# Converter_3V3-1V.net
KiCad netlist of a schematic drawn in Altium Designer
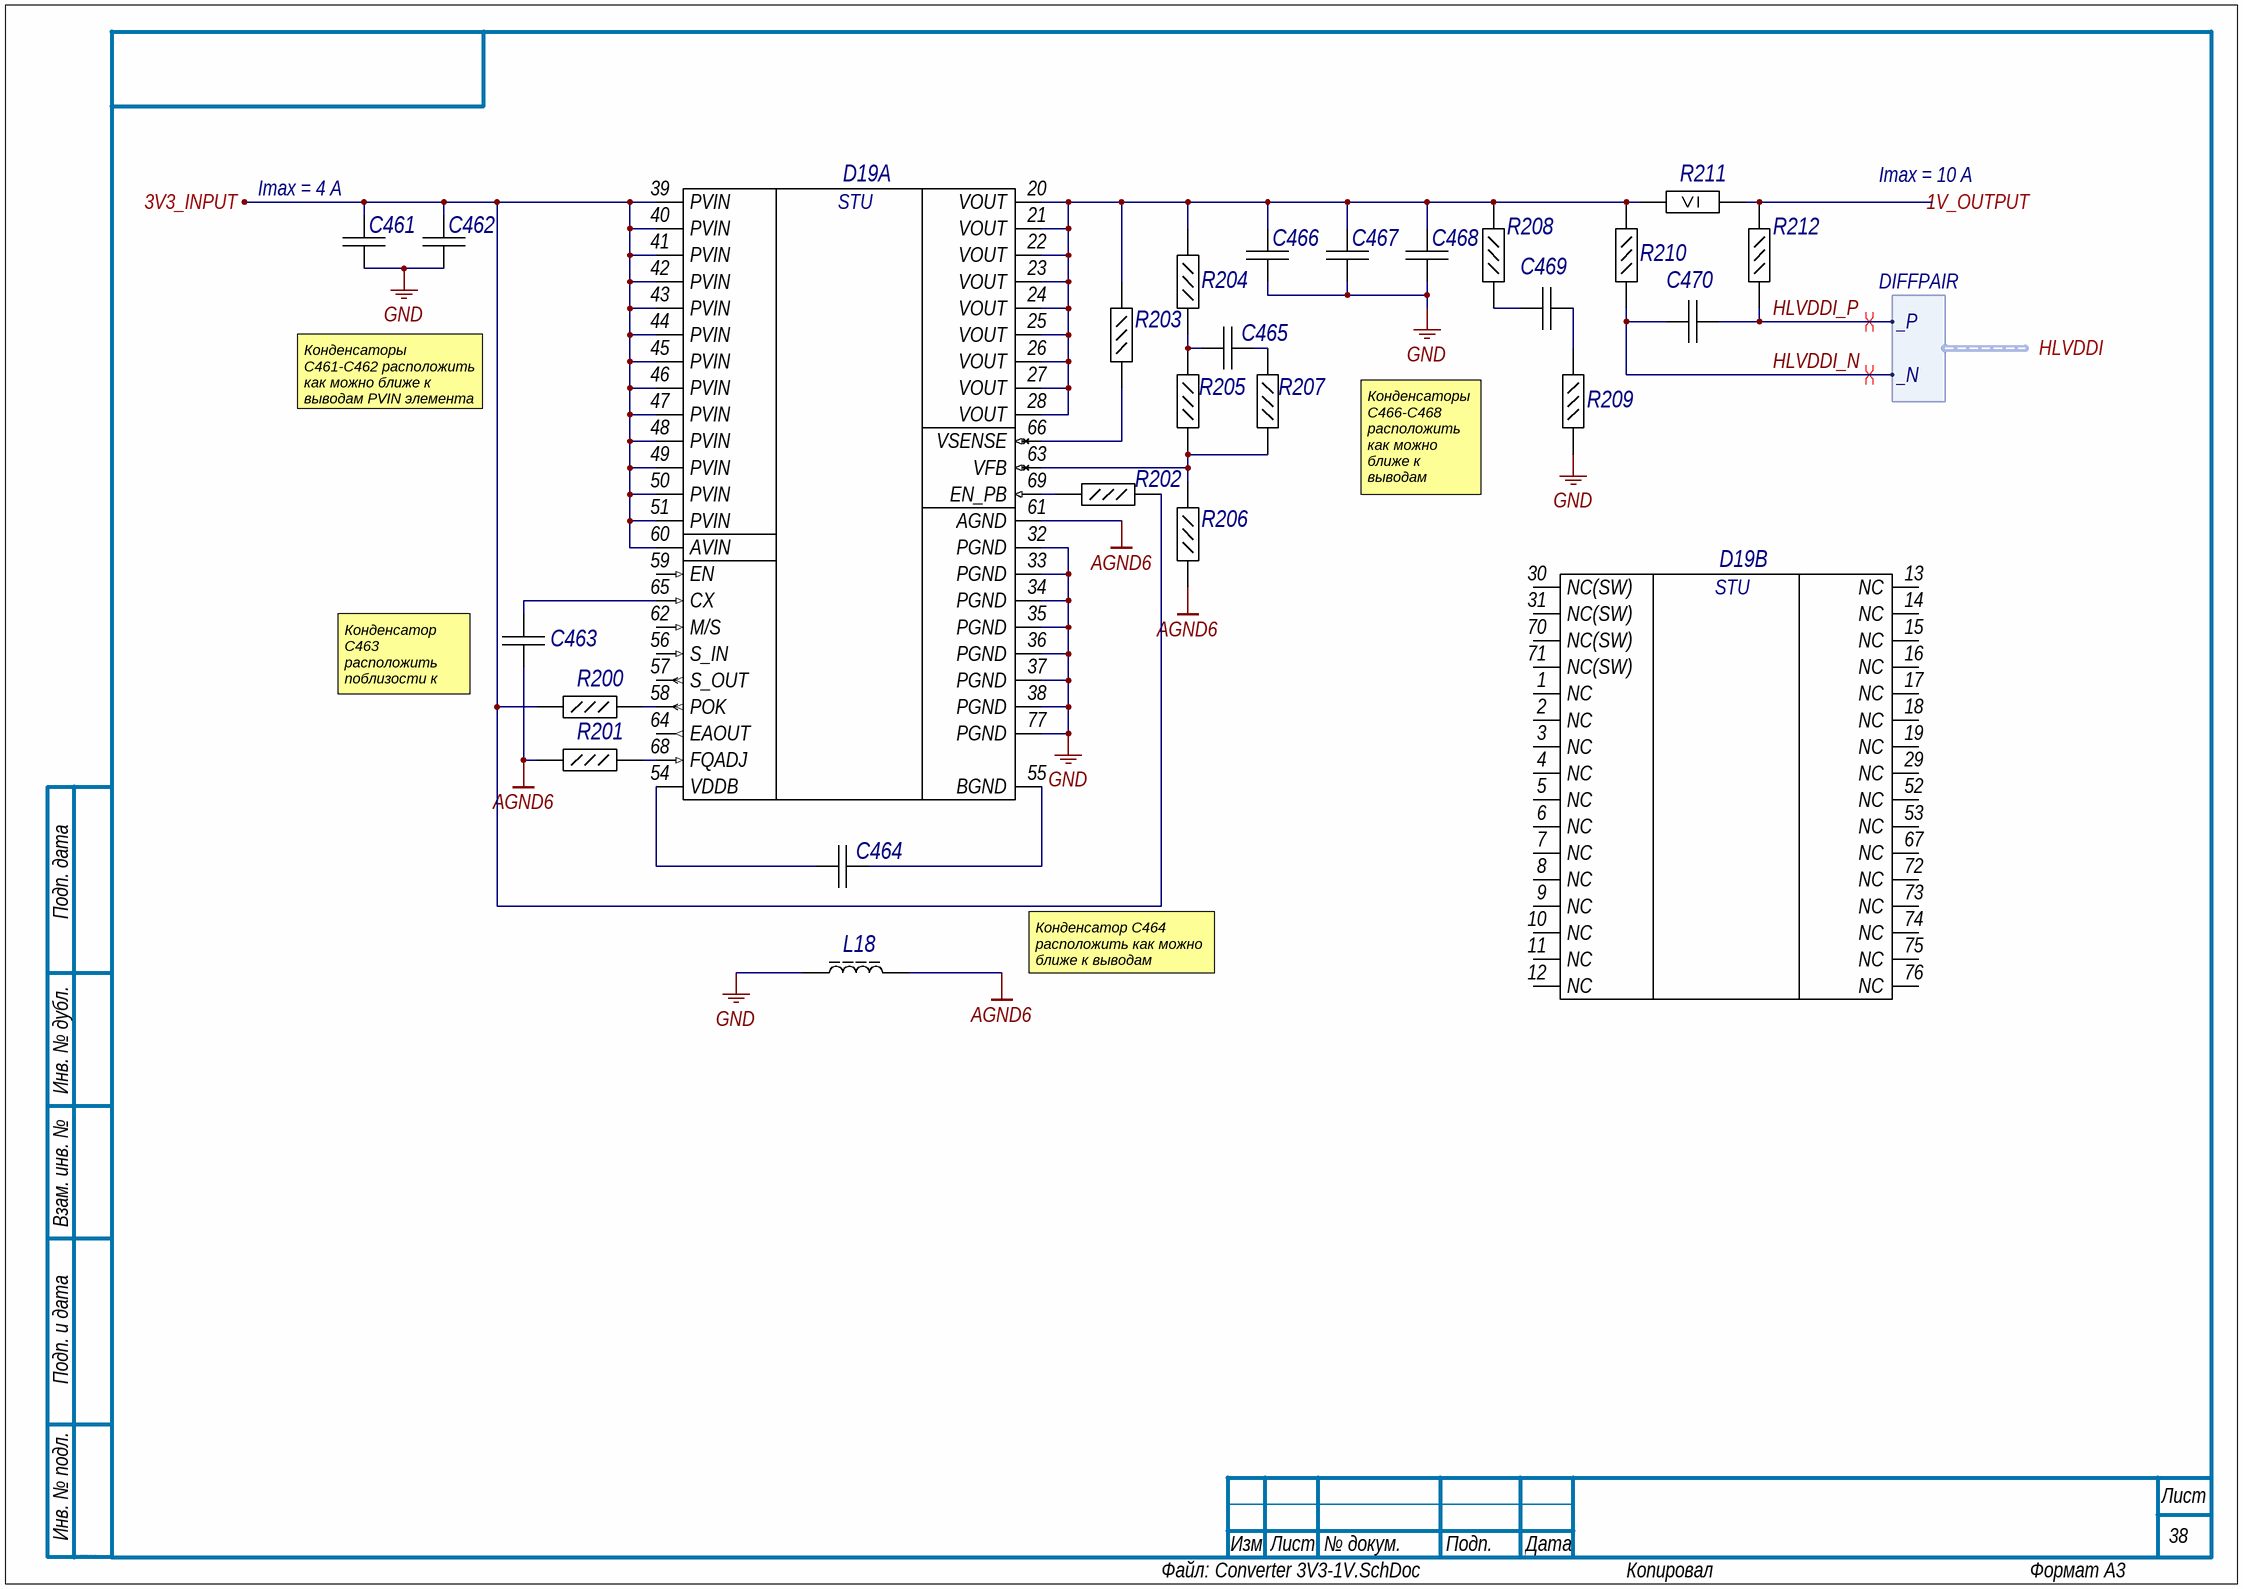
[diagram p0: Converter 3V3-1V.SchDoc]

(export (version "E")
  (design (tool "Eeschema 10.0.6"))
  (components
    (comp (ref "C461")
      (value "C3216X5R1A476M160AB")
      (footprint "CAPC3216X180X20ML20")
      (description "Chip Capacitor, 47 uF, +/- 20%, 10 V, -55 to 85 degC, 1206 (3216 Metric), RoHS, Tape and Reel")
      (fields (field (name "TOLERANCE") "20%"))
      (libsource (lib "MiniPC DB") (part "CAP_NP"))
    )
    (comp (ref "C462")
      (value "C3216X5R1A476M160AB")
      (footprint "CAPC3216X180X20ML20")
      (description "Chip Capacitor, 47 uF, +/- 20%, 10 V, -55 to 85 degC, 1206 (3216 Metric), RoHS, Tape and Reel")
      (fields (field (name "TOLERANCE") "20%"))
      (libsource (lib "MiniPC DB") (part "CAP_NP"))
    )
    (comp (ref "C463")
      (value "VJ0402Y153JXQPW1BC")
      (footprint "CAPC1005X55X23ML05T8")
      (description "Chip Capacitor, 15 nF, +/- 5%, 10 V, -55 to 125 degC, 0402 (1005 Metric), RoHS, Tape and Reel")
      (fields (field (name "TOLERANCE") "5%"))
      (libsource (lib "MiniPC DB") (part "CAP_NP"))
    )
    (comp (ref "C464")
      (value "GRM155R61A224KE19D")
      (footprint "CAPC1005X55X25NL05T10")
      (description "Chip Capacitor, 220 nF, +/- 10%, 10 V, -55 to 85 degC, 0402 (1005 Metric), RoHS, Tape and Reel")
      (fields (field (name "TOLERANCE") "10%") (field (name "MANUFACTURER") "Basic Passives"))
      (libsource (lib "MiniPC DB") (part "CAP_NP"))
    )
    (comp (ref "C465")
      (value "ECJ-0EC1H270J")
      (footprint "CAPC1005X55X20ML5T10")
      (description "Chip Capacitor, 27 pF, +/- 5%, 50 V, -55 to 125 degC, 0402 (1005 Metric), RoHS, Tape and Reel")
      (fields (field (name "TOLERANCE") "5%"))
      (libsource (lib "MiniPC DB") (part "CAP_NP"))
    )
    (comp (ref "C466")
      (value "C3216X5R1A476M160AB")
      (footprint "CAPC3216X180X20ML20")
      (description "Chip Capacitor, 47 uF, +/- 20%, 10 V, -55 to 85 degC, 1206 (3216 Metric), RoHS, Tape and Reel")
      (fields (field (name "TOLERANCE") "20%"))
      (libsource (lib "MiniPC DB") (part "CAP_NP"))
    )
    (comp (ref "C467")
      (value "C3216X5R1A476M160AB")
      (footprint "CAPC3216X180X20ML20")
      (description "Chip Capacitor, 47 uF, +/- 20%, 10 V, -55 to 85 degC, 1206 (3216 Metric), RoHS, Tape and Reel")
      (fields (field (name "TOLERANCE") "20%"))
      (libsource (lib "MiniPC DB") (part "CAP_NP"))
    )
    (comp (ref "C468")
      (value "C3216X5R1A476M160AB")
      (footprint "CAPC3216X180X20ML20")
      (description "Chip Capacitor, 47 uF, +/- 20%, 10 V, -55 to 85 degC, 1206 (3216 Metric), RoHS, Tape and Reel")
      (fields (field (name "TOLERANCE") "20%"))
      (libsource (lib "MiniPC DB") (part "CAP_NP"))
    )
    (comp (ref "C469")
      (value "GRM155R61A224KE19D")
      (footprint "CAPC1005X55X25NL05T10")
      (description "Chip Capacitor, 220 nF, +/- 10%, 10 V, -55 to 85 degC, 0402 (1005 Metric), RoHS, Tape and Reel")
      (fields (field (name "TOLERANCE") "10%") (field (name "MANUFACTURER") "Basic Passives"))
      (libsource (lib "MiniPC DB") (part "CAP_NP"))
    )
    (comp (ref "C470")
      (value "CGB2A1X5R1E105K033BC")
      (footprint "CAPC1005X33X10LL5")
      (description "Chip Capacitor, 1 uF, +/- 10%, 25 V, -55 to 85 degC, 0402 (1005 Metric), RoHS, Tape and Reel")
      (fields (field (name "TOLERANCE") "10%"))
      (libsource (lib "MiniPC DB") (part "CAP_NP"))
    )
    (comp (ref "D19")
      (value "EN63A0QI")
      (footprint "ALTR-QFN-76_A-305_V")
      (libsource (lib "MiniPC DB") (part "EN63A0QI"))
    )
    (comp (ref "L18")
      (value "742792609")
      (footprint "SMD-0603")
      (description "SMD EMI Suppression Ferrite Bead WE-CBF, Z = 30 Ohm")
      (libsource (lib "MiniPC DB") (part "Choke"))
    )
    (comp (ref "R200")
      (value "ERJ-2RKF1003X")
      (footprint "RESC1005X40X25LL05T05")
      (description "Chip Resistor, 100 KOhm, +/- 1%, 100 mW, -55 to 155 degC, 0402 (1005 Metric), RoHS, Tape and Reel")
      (fields (field (name "TOLERANCE") "1%") (field (name "MANUFACTURER") "Basic Passives"))
      (libsource (lib "MiniPC DB") (part "RES-0.05"))
    )
    (comp (ref "R201")
      (value "CRCW04023K57FKED")
      (footprint "RESC1005X40X25LL05T05")
      (description "Chip Resistor, 3.57 KOhm, +/- 1%, 63 mW, -55 to 155 degC, 0402 (1005 Metric), RoHS, Tape and Reel")
      (fields (field (name "TOLERANCE") "1%"))
      (libsource (lib "MiniPC DB") (part "RES-0.05"))
    )
    (comp (ref "R202")
      (value "ERJ-2RKF1002X")
      (footprint "RESC1005X40X25LL05T05")
      (description "Chip Resistor, 10 KOhm, +/- 1%, 100 mW, -55 to 155 degC, 0402 (1005 Metric), RoHS, Tape and Reel")
      (fields (field (name "TOLERANCE") "1%") (field (name "MANUFACTURER") "Basic Passives"))
      (libsource (lib "MiniPC DB") (part "RES-0.05"))
    )
    (comp (ref "R203")
      (value "ERJ-2GE0R00X")
      (footprint "RESC1005X40X25LL05T05")
      (description "Chip Resistor, 0 mOhm, +/- 5%, 100 mW, -55 to 155 degC, 0402 (1005 Metric), RoHS, Tape and Reel")
      (fields (field (name "TOLERANCE") "5%") (field (name "MANUFACTURER") "Basic Passives"))
      (libsource (lib "") (part "RES-0.05_2"))
    )
    (comp (ref "R204")
      (value "ERJ-2GE0R00X")
      (footprint "RESC1005X40X25LL05T05")
      (description "Chip Resistor, 0 mOhm, +/- 5%, 100 mW, -55 to 155 degC, 0402 (1005 Metric), RoHS, Tape and Reel")
      (fields (field (name "TOLERANCE") "5%") (field (name "MANUFACTURER") "Basic Passives"))
      (libsource (lib "") (part "RES-0.05_1"))
    )
    (comp (ref "R205")
      (value "CRCW0402160KFKED")
      (footprint "RESC1005X40X25LL05T05")
      (description "Chip Resistor, 160 KOhm, +/- 1%, 63 mW, -55 to 155 degC, 0402 (1005 Metric), RoHS, Tape and Reel")
      (fields (field (name "TOLERANCE") "1%") (field (name "MANUFACTURER") "Basic Passives"))
      (libsource (lib "") (part "RES-0.05_1"))
    )
    (comp (ref "R206")
      (value "ERJ-2RKF2263X")
      (footprint "RESC1005X40X25LL05T05")
      (description "Chip Resistor, 226 KOhm, +/- 1%, 100 mW, -55 to 155 degC, 0402 (1005 Metric), RoHS, Tape and Reel")
      (fields (field (name "TOLERANCE") "1%") (field (name "MANUFACTURER") "Basic Passives"))
      (libsource (lib "") (part "RES-0.05_1"))
    )
    (comp (ref "R207")
      (value "ERJ-2RKF1202X")
      (footprint "RESC1005X40X25LL05T05")
      (description "Chip Resistor, 12 KOhm, +/- 1%, 0.1 W, -55 to 155 degC, 0402 (1005 Metric), RoHS, Tape and Reel")
      (fields (field (name "TOLERANCE") "1%"))
      (libsource (lib "") (part "RES-0.05_1"))
    )
    (comp (ref "R208")
      (value "ERJ-2RKF1000X")
      (footprint "RESC1005X40X25LL05T05")
      (description "Chip Resistor, 100 Ohm, +/- 1%, 100 mW, -55 to 155 degC, 0402 (1005 Metric), RoHS, Tape and Reel")
      (fields (field (name "TOLERANCE") "1%") (field (name "MANUFACTURER") "Basic Passives"))
      (libsource (lib "") (part "RES-0.05_1"))
    )
    (comp (ref "R209")
      (value "ERJ-2RKF1000X")
      (footprint "RESC1005X40X25LL05T05")
      (description "Chip Resistor, 100 Ohm, +/- 1%, 100 mW, -55 to 155 degC, 0402 (1005 Metric), RoHS, Tape and Reel")
      (fields (field (name "TOLERANCE") "1%") (field (name "MANUFACTURER") "Basic Passives"))
      (libsource (lib "") (part "RES-0.05_2"))
    )
    (comp (ref "R210")
      (value "ERJ-2RKF1002X")
      (footprint "RESC1005X40X25LL05T05")
      (description "Chip Resistor, 10 KOhm, +/- 1%, 100 mW, -55 to 155 degC, 0402 (1005 Metric), RoHS, Tape and Reel")
      (fields (field (name "TOLERANCE") "1%") (field (name "MANUFACTURER") "Basic Passives"))
      (libsource (lib "") (part "RES-0.05_2"))
    )
    (comp (ref "R211")
      (value "CSS2725FTL250")
      (footprint "STAC-CSS2725-099H_V")
      (description "Chip Resistor, 0.25 mOhm, +/- 1%, 4 W, -55 to 225 degC, 2725 (6865 Metric), RoHS, Tape and Reel")
      (fields (field (name "TOLERANCE") "1%"))
      (libsource (lib "MiniPC DB") (part "RES-4"))
    )
    (comp (ref "R212")
      (value "ERJ-2RKF1002X")
      (footprint "RESC1005X40X25LL05T05")
      (description "Chip Resistor, 10 KOhm, +/- 1%, 100 mW, -55 to 155 degC, 0402 (1005 Metric), RoHS, Tape and Reel")
      (fields (field (name "TOLERANCE") "1%") (field (name "MANUFACTURER") "Basic Passives"))
      (libsource (lib "") (part "RES-0.05_2"))
    )
  )
  (nets
    (net (code "2") (name "/1V_OUTPUT") (class "Default")
      (node (ref "R211") (pin "1") (pinfunction "1_1") (pintype "passive"))
      (node (ref "R212") (pin "2") (pinfunction "2_2") (pintype "passive"))
    )
    (net (code "3") (name "/3V3_INPUT") (class "Default")
      (node (ref "C461") (pin "2") (pinfunction "2_2") (pintype "passive"))
      (node (ref "C462") (pin "2") (pinfunction "2_2") (pintype "passive"))
      (node (ref "D19") (pin "39") (pinfunction "PVIN_39") (pintype "power_in"))
      (node (ref "D19") (pin "40") (pinfunction "PVIN_40") (pintype "power_in"))
      (node (ref "D19") (pin "41") (pinfunction "PVIN_41") (pintype "power_in"))
      (node (ref "D19") (pin "42") (pinfunction "PVIN_42") (pintype "power_in"))
      (node (ref "D19") (pin "43") (pinfunction "PVIN_43") (pintype "power_in"))
      (node (ref "D19") (pin "44") (pinfunction "PVIN_44") (pintype "power_in"))
      (node (ref "D19") (pin "45") (pinfunction "PVIN_45") (pintype "power_in"))
      (node (ref "D19") (pin "46") (pinfunction "PVIN_46") (pintype "power_in"))
      (node (ref "D19") (pin "47") (pinfunction "PVIN_47") (pintype "power_in"))
      (node (ref "D19") (pin "48") (pinfunction "PVIN_48") (pintype "power_in"))
      (node (ref "D19") (pin "49") (pinfunction "PVIN_49") (pintype "power_in"))
      (node (ref "D19") (pin "50") (pinfunction "PVIN_50") (pintype "power_in"))
      (node (ref "D19") (pin "51") (pinfunction "PVIN_51") (pintype "power_in"))
      (node (ref "D19") (pin "60") (pinfunction "AVIN_60") (pintype "power_in"))
      (node (ref "R200") (pin "2") (pinfunction "2_2") (pintype "passive"))
      (node (ref "R202") (pin "1") (pinfunction "1_1") (pintype "passive"))
    )
    (net (code "4") (name "/HLVDDI_N") (class "Default")
      (node (ref "C470") (pin "1") (pinfunction "1_1") (pintype "passive"))
      (node (ref "R210") (pin "1") (pinfunction "1_1") (pintype "passive"))
    )
    (net (code "5") (name "/HLVDDI_P") (class "Default")
      (node (ref "C470") (pin "2") (pinfunction "2_2") (pintype "passive"))
      (node (ref "R212") (pin "1") (pinfunction "1_1") (pintype "passive"))
    )
    (net (code "7") (name "AGND6") (class "Default")
      (node (ref "C463") (pin "1") (pinfunction "1_1") (pintype "passive"))
      (node (ref "D19") (pin "61") (pinfunction "AGND_61") (pintype "power_in"))
      (node (ref "L18") (pin "2") (pinfunction "2_2") (pintype "passive"))
      (node (ref "R201") (pin "2") (pinfunction "2_2") (pintype "passive"))
      (node (ref "R206") (pin "2") (pinfunction "2_2") (pintype "passive"))
    )
    (net (code "8") (name "GND") (class "Default")
      (node (ref "C461") (pin "1") (pinfunction "1_1") (pintype "passive"))
      (node (ref "C462") (pin "1") (pinfunction "1_1") (pintype "passive"))
      (node (ref "C466") (pin "1") (pinfunction "1_1") (pintype "passive"))
      (node (ref "C467") (pin "1") (pinfunction "1_1") (pintype "passive"))
      (node (ref "C468") (pin "1") (pinfunction "1_1") (pintype "passive"))
      (node (ref "D19") (pin "32") (pinfunction "PGND_32") (pintype "power_in"))
      (node (ref "D19") (pin "33") (pinfunction "PGND_33") (pintype "power_in"))
      (node (ref "D19") (pin "34") (pinfunction "PGND_34") (pintype "power_in"))
      (node (ref "D19") (pin "35") (pinfunction "PGND_35") (pintype "power_in"))
      (node (ref "D19") (pin "36") (pinfunction "PGND_36") (pintype "power_in"))
      (node (ref "D19") (pin "37") (pinfunction "PGND_37") (pintype "power_in"))
      (node (ref "D19") (pin "38") (pinfunction "PGND_38") (pintype "power_in"))
      (node (ref "D19") (pin "77") (pinfunction "PGND_77") (pintype "power_in"))
      (node (ref "L18") (pin "1") (pinfunction "1_1") (pintype "passive"))
      (node (ref "R209") (pin "1") (pinfunction "1_1") (pintype "passive"))
    )
    (net (code "9") (name "Net-(C465-Pad1)") (class "Default")
      (node (ref "C465") (pin "1") (pinfunction "1_1") (pintype "passive"))
      (node (ref "R204") (pin "2") (pinfunction "2_2") (pintype "passive"))
      (node (ref "R205") (pin "1") (pinfunction "1_1") (pintype "passive"))
    )
    (net (code "10") (name "Net-(C465-Pad2)") (class "Default")
      (node (ref "C465") (pin "2") (pinfunction "2_2") (pintype "passive"))
      (node (ref "R207") (pin "1") (pinfunction "1_1") (pintype "passive"))
    )
    (net (code "11") (name "Net-(C466-Pad2)") (class "Default")
      (node (ref "C466") (pin "2") (pinfunction "2_2") (pintype "passive"))
      (node (ref "C467") (pin "2") (pinfunction "2_2") (pintype "passive"))
      (node (ref "C468") (pin "2") (pinfunction "2_2") (pintype "passive"))
      (node (ref "D19") (pin "20") (pinfunction "VOUT_20") (pintype "power_in"))
      (node (ref "D19") (pin "21") (pinfunction "VOUT_21") (pintype "power_in"))
      (node (ref "D19") (pin "22") (pinfunction "VOUT_22") (pintype "power_in"))
      (node (ref "D19") (pin "23") (pinfunction "VOUT_23") (pintype "power_in"))
      (node (ref "D19") (pin "24") (pinfunction "VOUT_24") (pintype "power_in"))
      (node (ref "D19") (pin "25") (pinfunction "VOUT_25") (pintype "power_in"))
      (node (ref "D19") (pin "26") (pinfunction "VOUT_26") (pintype "power_in"))
      (node (ref "D19") (pin "27") (pinfunction "VOUT_27") (pintype "power_in"))
      (node (ref "D19") (pin "28") (pinfunction "VOUT_28") (pintype "power_in"))
      (node (ref "R203") (pin "2") (pinfunction "2_2") (pintype "passive"))
      (node (ref "R204") (pin "1") (pinfunction "1_1") (pintype "passive"))
      (node (ref "R208") (pin "1") (pinfunction "1_1") (pintype "passive"))
      (node (ref "R210") (pin "2") (pinfunction "2_2") (pintype "passive"))
      (node (ref "R211") (pin "2") (pinfunction "2_2") (pintype "passive"))
    )
    (net (code "12") (name "Net-(C469-Pad1)") (class "Default")
      (node (ref "C469") (pin "1") (pinfunction "1_1") (pintype "passive"))
      (node (ref "R208") (pin "2") (pinfunction "2_2") (pintype "passive"))
    )
    (net (code "13") (name "Net-(C469-Pad2)") (class "Default")
      (node (ref "C469") (pin "2") (pinfunction "2_2") (pintype "passive"))
      (node (ref "R209") (pin "2") (pinfunction "2_2") (pintype "passive"))
    )
    (net (code "14") (name "Net-(D19A-BGND)") (class "Default")
      (node (ref "C464") (pin "1") (pinfunction "1_1") (pintype "passive"))
      (node (ref "D19") (pin "55") (pinfunction "BGND_55") (pintype "power_in"))
    )
    (net (code "15") (name "Net-(D19A-CX)") (class "Default")
      (node (ref "C463") (pin "2") (pinfunction "2_2") (pintype "passive"))
      (node (ref "D19") (pin "65") (pinfunction "CX_65") (pintype "input"))
    )
    (net (code "16") (name "Net-(D19A-EN_PB)") (class "Default")
      (node (ref "D19") (pin "69") (pinfunction "EN_PB_69") (pintype "input"))
      (node (ref "R202") (pin "2") (pinfunction "2_2") (pintype "passive"))
    )
    (net (code "17") (name "Net-(D19A-FQADJ)") (class "Default")
      (node (ref "D19") (pin "68") (pinfunction "FQADJ_68") (pintype "input"))
      (node (ref "R201") (pin "1") (pinfunction "1_1") (pintype "passive"))
    )
    (net (code "18") (name "Net-(D19A-POK)") (class "Default")
      (node (ref "D19") (pin "58") (pinfunction "POK_58") (pintype "output"))
      (node (ref "R200") (pin "1") (pinfunction "1_1") (pintype "passive"))
    )
    (net (code "19") (name "Net-(D19A-VDDB)") (class "Default")
      (node (ref "C464") (pin "2") (pinfunction "2_2") (pintype "passive"))
      (node (ref "D19") (pin "54") (pinfunction "VDDB_54") (pintype "power_in"))
    )
    (net (code "20") (name "Net-(D19A-VFB)") (class "Default")
      (node (ref "D19") (pin "63") (pinfunction "VFB_63") (pintype "input"))
      (node (ref "R205") (pin "2") (pinfunction "2_2") (pintype "passive"))
      (node (ref "R206") (pin "1") (pinfunction "1_1") (pintype "passive"))
      (node (ref "R207") (pin "2") (pinfunction "2_2") (pintype "passive"))
    )
    (net (code "21") (name "Net-(D19A-VSENSE)") (class "Default")
      (node (ref "D19") (pin "66") (pinfunction "VSENSE_66") (pintype "input"))
      (node (ref "R203") (pin "1") (pinfunction "1_1") (pintype "passive"))
    )
    (net (code "22") (name "unconnected-(D19A-EAOUT-Pad64)") (class "Default")
      (node (ref "D19") (pin "64") (pinfunction "EAOUT_64") (pintype "output"))
    )
    (net (code "23") (name "unconnected-(D19A-EN-Pad59)") (class "Default")
      (node (ref "D19") (pin "59") (pinfunction "EN_59") (pintype "input"))
    )
    (net (code "24") (name "unconnected-(D19A-M{slash}S-Pad62)") (class "Default")
      (node (ref "D19") (pin "62") (pinfunction "M/S_62") (pintype "input"))
    )
    (net (code "25") (name "unconnected-(D19A-S_IN-Pad56)") (class "Default")
      (node (ref "D19") (pin "56") (pinfunction "S_IN_56") (pintype "input"))
    )
    (net (code "26") (name "unconnected-(D19A-S_OUT-Pad57)") (class "Default")
      (node (ref "D19") (pin "57") (pinfunction "S_OUT_57") (pintype "output"))
    )
    (net (code "27") (name "unconnected-(D19B-NC(SW)-Pad30)") (class "Default")
      (node (ref "D19") (pin "30") (pinfunction "NC(SW)_30") (pintype "passive"))
    )
    (net (code "28") (name "unconnected-(D19B-NC(SW)-Pad31)") (class "Default")
      (node (ref "D19") (pin "31") (pinfunction "NC(SW)_31") (pintype "passive"))
    )
    (net (code "29") (name "unconnected-(D19B-NC(SW)-Pad70)") (class "Default")
      (node (ref "D19") (pin "70") (pinfunction "NC(SW)_70") (pintype "passive"))
    )
    (net (code "30") (name "unconnected-(D19B-NC(SW)-Pad71)") (class "Default")
      (node (ref "D19") (pin "71") (pinfunction "NC(SW)_71") (pintype "passive"))
    )
    (net (code "31") (name "unconnected-(D19B-NC-Pad1)") (class "Default")
      (node (ref "D19") (pin "1") (pinfunction "NC_1") (pintype "passive"))
    )
    (net (code "32") (name "unconnected-(D19B-NC-Pad2)") (class "Default")
      (node (ref "D19") (pin "2") (pinfunction "NC_2") (pintype "passive"))
    )
    (net (code "33") (name "unconnected-(D19B-NC-Pad3)") (class "Default")
      (node (ref "D19") (pin "3") (pinfunction "NC_3") (pintype "passive"))
    )
    (net (code "34") (name "unconnected-(D19B-NC-Pad4)") (class "Default")
      (node (ref "D19") (pin "4") (pinfunction "NC_4") (pintype "passive"))
    )
    (net (code "35") (name "unconnected-(D19B-NC-Pad5)") (class "Default")
      (node (ref "D19") (pin "5") (pinfunction "NC_5") (pintype "passive"))
    )
    (net (code "36") (name "unconnected-(D19B-NC-Pad6)") (class "Default")
      (node (ref "D19") (pin "6") (pinfunction "NC_6") (pintype "passive"))
    )
    (net (code "37") (name "unconnected-(D19B-NC-Pad7)") (class "Default")
      (node (ref "D19") (pin "7") (pinfunction "NC_7") (pintype "passive"))
    )
    (net (code "38") (name "unconnected-(D19B-NC-Pad8)") (class "Default")
      (node (ref "D19") (pin "8") (pinfunction "NC_8") (pintype "passive"))
    )
    (net (code "39") (name "unconnected-(D19B-NC-Pad9)") (class "Default")
      (node (ref "D19") (pin "9") (pinfunction "NC_9") (pintype "passive"))
    )
    (net (code "40") (name "unconnected-(D19B-NC-Pad10)") (class "Default")
      (node (ref "D19") (pin "10") (pinfunction "NC_10") (pintype "passive"))
    )
    (net (code "41") (name "unconnected-(D19B-NC-Pad11)") (class "Default")
      (node (ref "D19") (pin "11") (pinfunction "NC_11") (pintype "passive"))
    )
    (net (code "42") (name "unconnected-(D19B-NC-Pad12)") (class "Default")
      (node (ref "D19") (pin "12") (pinfunction "NC_12") (pintype "passive"))
    )
    (net (code "43") (name "unconnected-(D19B-NC-Pad13)") (class "Default")
      (node (ref "D19") (pin "13") (pinfunction "NC_13") (pintype "passive"))
    )
    (net (code "44") (name "unconnected-(D19B-NC-Pad14)") (class "Default")
      (node (ref "D19") (pin "14") (pinfunction "NC_14") (pintype "passive"))
    )
    (net (code "45") (name "unconnected-(D19B-NC-Pad15)") (class "Default")
      (node (ref "D19") (pin "15") (pinfunction "NC_15") (pintype "passive"))
    )
    (net (code "46") (name "unconnected-(D19B-NC-Pad16)") (class "Default")
      (node (ref "D19") (pin "16") (pinfunction "NC_16") (pintype "passive"))
    )
    (net (code "47") (name "unconnected-(D19B-NC-Pad17)") (class "Default")
      (node (ref "D19") (pin "17") (pinfunction "NC_17") (pintype "passive"))
    )
    (net (code "48") (name "unconnected-(D19B-NC-Pad18)") (class "Default")
      (node (ref "D19") (pin "18") (pinfunction "NC_18") (pintype "passive"))
    )
    (net (code "49") (name "unconnected-(D19B-NC-Pad19)") (class "Default")
      (node (ref "D19") (pin "19") (pinfunction "NC_19") (pintype "passive"))
    )
    (net (code "50") (name "unconnected-(D19B-NC-Pad29)") (class "Default")
      (node (ref "D19") (pin "29") (pinfunction "NC_29") (pintype "passive"))
    )
    (net (code "51") (name "unconnected-(D19B-NC-Pad52)") (class "Default")
      (node (ref "D19") (pin "52") (pinfunction "NC_52") (pintype "passive"))
    )
    (net (code "52") (name "unconnected-(D19B-NC-Pad53)") (class "Default")
      (node (ref "D19") (pin "53") (pinfunction "NC_53") (pintype "passive"))
    )
    (net (code "53") (name "unconnected-(D19B-NC-Pad67)") (class "Default")
      (node (ref "D19") (pin "67") (pinfunction "NC_67") (pintype "passive"))
    )
    (net (code "54") (name "unconnected-(D19B-NC-Pad72)") (class "Default")
      (node (ref "D19") (pin "72") (pinfunction "NC_72") (pintype "passive"))
    )
    (net (code "55") (name "unconnected-(D19B-NC-Pad73)") (class "Default")
      (node (ref "D19") (pin "73") (pinfunction "NC_73") (pintype "passive"))
    )
    (net (code "56") (name "unconnected-(D19B-NC-Pad74)") (class "Default")
      (node (ref "D19") (pin "74") (pinfunction "NC_74") (pintype "passive"))
    )
    (net (code "57") (name "unconnected-(D19B-NC-Pad75)") (class "Default")
      (node (ref "D19") (pin "75") (pinfunction "NC_75") (pintype "passive"))
    )
    (net (code "58") (name "unconnected-(D19B-NC-Pad76)") (class "Default")
      (node (ref "D19") (pin "76") (pinfunction "NC_76") (pintype "passive"))
    )
  )
)
